# PwrSup.net
KiCad netlist of a schematic drawn in Altium Designer
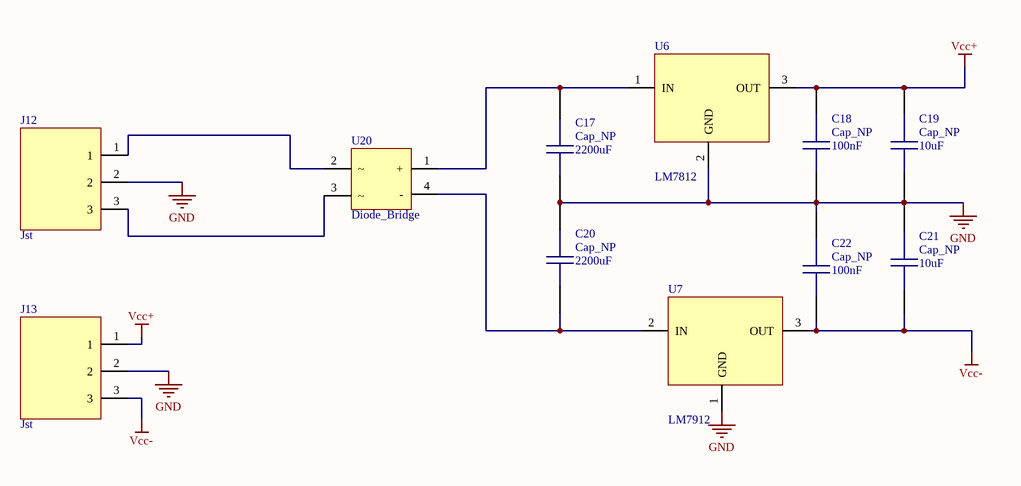
[diagram p0: PwrSup.SchDoc]

(export (version "E")
  (design (tool "Eeschema 10.0.6"))
  (components
    (comp (ref "C17")
      (value "Cap_NP")
      (footprint "Cap NP")
      (fields (field (name "ALTIUM_VALUE") "2200uF"))
      (libsource (lib "Funcgen") (part "Cap_NP"))
    )
    (comp (ref "C18")
      (value "Cap_NP")
      (footprint "Cap NP")
      (fields (field (name "ALTIUM_VALUE") "100nF"))
      (libsource (lib "Funcgen") (part "Cap_NP"))
    )
    (comp (ref "C19")
      (value "Cap_NP")
      (footprint "Cap NP")
      (fields (field (name "ALTIUM_VALUE") "10uF"))
      (libsource (lib "Funcgen") (part "Cap_NP"))
    )
    (comp (ref "C20")
      (value "Cap_NP")
      (footprint "Cap NP")
      (fields (field (name "ALTIUM_VALUE") "2200uF"))
      (libsource (lib "Funcgen") (part "Cap_NP"))
    )
    (comp (ref "C21")
      (value "Cap_NP")
      (footprint "Cap NP")
      (fields (field (name "ALTIUM_VALUE") "10uF"))
      (libsource (lib "Funcgen") (part "Cap_NP"))
    )
    (comp (ref "C22")
      (value "Cap_NP")
      (footprint "Cap NP")
      (fields (field (name "ALTIUM_VALUE") "100nF"))
      (libsource (lib "Funcgen") (part "Cap_NP"))
    )
    (comp (ref "J12") (value "Jst") (footprint "Funcgen:Jst_3p") (libsource (lib "Funcgen") (part "Jst_3p")))
    (comp (ref "J13") (value "Jst") (footprint "Funcgen:Jst_3p") (libsource (lib "Funcgen") (part "Jst_3p")))
    (comp (ref "U6") (value "LM7812") (footprint "TIP 31") (libsource (lib "Funcgen") (part "LM7812")))
    (comp (ref "U7") (value "LM7912") (footprint "TIP 31") (libsource (lib "Funcgen") (part "LM7912")))
    (comp (ref "U20")
      (value "Diode_Bridge")
      (footprint "Diode Bridge 2")
      (libsource (lib "Funcgen") (part "Diode_Bridge"))
    )
  )
  (nets
    (net (code "1") (name "GND") (class "Default")
      (node (ref "C17") (pin "1") (pinfunction "1_1") (pintype "passive"))
      (node (ref "C18") (pin "1") (pinfunction "1_1") (pintype "passive"))
      (node (ref "C19") (pin "1") (pinfunction "1_1") (pintype "passive"))
      (node (ref "C20") (pin "2") (pinfunction "2_2") (pintype "passive"))
      (node (ref "C21") (pin "2") (pinfunction "2_2") (pintype "passive"))
      (node (ref "C22") (pin "2") (pinfunction "2_2") (pintype "passive"))
      (node (ref "J12") (pin "2") (pinfunction "2_2") (pintype "passive"))
      (node (ref "J13") (pin "2") (pinfunction "2_2") (pintype "passive"))
      (node (ref "U6") (pin "2") (pinfunction "GND_2") (pintype "passive"))
      (node (ref "U7") (pin "1") (pinfunction "GND_1") (pintype "passive"))
    )
    (net (code "2") (name "Net-(J12-Pad1)") (class "Default")
      (node (ref "J12") (pin "1") (pinfunction "1_1") (pintype "passive"))
      (node (ref "U20") (pin "2") (pinfunction "~_2") (pintype "passive"))
    )
    (net (code "3") (name "Net-(J12-Pad3)") (class "Default")
      (node (ref "J12") (pin "3") (pinfunction "3_3") (pintype "passive"))
      (node (ref "U20") (pin "3") (pinfunction "~_3") (pintype "passive"))
    )
    (net (code "4") (name "Net-(U20-+)") (class "Default")
      (node (ref "C17") (pin "2") (pinfunction "2_2") (pintype "passive"))
      (node (ref "U20") (pin "1") (pinfunction "+_1") (pintype "passive"))
      (node (ref "U6") (pin "1") (pinfunction "IN_1") (pintype "passive"))
    )
    (net (code "5") (name "Net-(U20--)") (class "Default")
      (node (ref "C20") (pin "1") (pinfunction "1_1") (pintype "passive"))
      (node (ref "U20") (pin "4") (pinfunction "-_4") (pintype "passive"))
      (node (ref "U7") (pin "2") (pinfunction "IN_2") (pintype "passive"))
    )
    (net (code "6") (name "Vcc+") (class "Default")
      (node (ref "C18") (pin "2") (pinfunction "2_2") (pintype "passive"))
      (node (ref "C19") (pin "2") (pinfunction "2_2") (pintype "passive"))
      (node (ref "J13") (pin "1") (pinfunction "1_1") (pintype "passive"))
      (node (ref "U6") (pin "3") (pinfunction "OUT_3") (pintype "passive"))
    )
    (net (code "7") (name "Vcc-") (class "Default")
      (node (ref "C21") (pin "1") (pinfunction "1_1") (pintype "passive"))
      (node (ref "C22") (pin "1") (pinfunction "1_1") (pintype "passive"))
      (node (ref "J13") (pin "3") (pinfunction "3_3") (pintype "passive"))
      (node (ref "U7") (pin "3") (pinfunction "OUT_3") (pintype "passive"))
    )
  )
)
